# ttl2rs485.net
KiCad netlist of a schematic drawn in Altium Designer
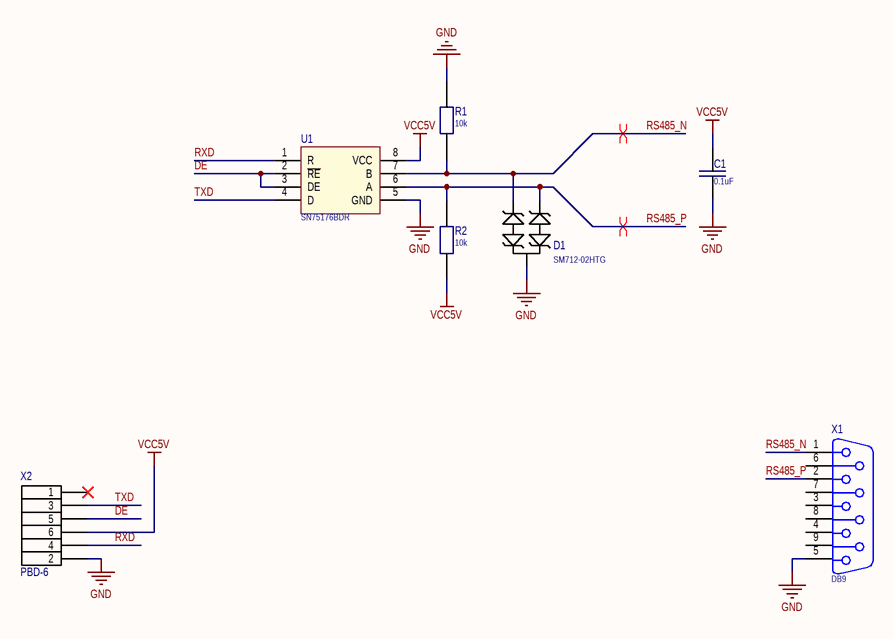
[diagram p0: ttl2rs485.SchDoc]

(export (version "E")
  (design (tool "Eeschema 10.0.6"))
  (components
    (comp (ref "C1")
      (value "0.1uF")
      (footprint "C_0603")
      (description "Capacitor")
      (fields (field (name "PART NUMBER") "CC0603KPX7R9BB104"))
      (libsource (lib "capacitors") (part "CAP_SMD"))
    )
    (comp (ref "D1")
      (value "SM712-02HTG")
      (footprint "diode:SOT23")
      (description "ESD")
      (libsource (lib "diode") (part "ESD"))
    )
    (comp (ref "R1")
      (value "10k")
      (footprint "R_0603")
      (description "Resistor")
      (fields (field (name "PART NUMBER") "RC0603FR-0710KL"))
      (libsource (lib "resistors") (part "RES_SMD"))
    )
    (comp (ref "R2")
      (value "10k")
      (footprint "R_0603")
      (description "Resistor")
      (fields (field (name "PART NUMBER") "RC0603FR-0710KL"))
      (libsource (lib "resistors") (part "RES_SMD"))
    )
    (comp (ref "U1")
      (value "SN75176BDR")
      (footprint "SO-8")
      (description "RS485 Half Duplex Convertor")
      (libsource (lib "discret_ic") (part "SN75176BDR"))
    )
    (comp (ref "X1")
      (value "DB9")
      (footprint "DB9_template")
      (description "Connector")
      (libsource (lib "connectors_socets") (part "DB9_template"))
    )
    (comp (ref "X2")
      (value "PBD-6")
      (footprint "PBD-6-sideways")
      (description "Header, 6-Pin, Dual row")
      (libsource (lib "connectors_socets") (part "PBD-6"))
    )
  )
  (nets
    (net (code "1") (name "/DE") (class "Default")
      (node (ref "U1") (pin "2") (pinfunction "~{RE}_2") (pintype "passive"))
      (node (ref "U1") (pin "3") (pinfunction "DE_3") (pintype "passive"))
      (node (ref "X2") (pin "5") (pinfunction "5_5") (pintype "passive"))
    )
    (net (code "2") (name "/RS485_N") (class "Default")
      (node (ref "D1") (pin "1") (pinfunction "1_1") (pintype "passive"))
      (node (ref "R1") (pin "1") (pinfunction "1_1") (pintype "passive"))
      (node (ref "U1") (pin "7") (pinfunction "B_7") (pintype "passive"))
      (node (ref "X1") (pin "1") (pinfunction "1_1") (pintype "passive"))
    )
    (net (code "3") (name "/RS485_P") (class "Default")
      (node (ref "D1") (pin "2") (pinfunction "2_2") (pintype "passive"))
      (node (ref "R2") (pin "2") (pinfunction "2_2") (pintype "passive"))
      (node (ref "U1") (pin "6") (pinfunction "A_6") (pintype "passive"))
      (node (ref "X1") (pin "2") (pinfunction "2_2") (pintype "passive"))
    )
    (net (code "4") (name "/RXD") (class "Default")
      (node (ref "U1") (pin "1") (pinfunction "R_1") (pintype "passive"))
      (node (ref "X2") (pin "4") (pinfunction "4_4") (pintype "passive"))
    )
    (net (code "5") (name "/TXD") (class "Default")
      (node (ref "U1") (pin "4") (pinfunction "D_4") (pintype "passive"))
      (node (ref "X2") (pin "3") (pinfunction "3_3") (pintype "passive"))
    )
    (net (code "6") (name "GND") (class "Default")
      (node (ref "C1") (pin "1") (pinfunction "1_1") (pintype "passive"))
      (node (ref "D1") (pin "3") (pinfunction "3_3") (pintype "passive"))
      (node (ref "R1") (pin "2") (pinfunction "2_2") (pintype "passive"))
      (node (ref "U1") (pin "5") (pinfunction "GND_5") (pintype "passive"))
      (node (ref "X1") (pin "5") (pinfunction "5_5") (pintype "passive"))
      (node (ref "X2") (pin "2") (pinfunction "2_2") (pintype "passive"))
    )
    (net (code "7") (name "VCC5V") (class "Default")
      (node (ref "C1") (pin "2") (pinfunction "2_2") (pintype "passive"))
      (node (ref "R2") (pin "1") (pinfunction "1_1") (pintype "passive"))
      (node (ref "U1") (pin "8") (pinfunction "VCC_8") (pintype "passive"))
      (node (ref "X2") (pin "6") (pinfunction "6_6") (pintype "passive"))
    )
    (net (code "8") (name "unconnected-(X1-Pad3)") (class "Default")
      (node (ref "X1") (pin "3") (pinfunction "3_3") (pintype "passive"))
    )
    (net (code "9") (name "unconnected-(X1-Pad4)") (class "Default")
      (node (ref "X1") (pin "4") (pinfunction "4_4") (pintype "passive"))
    )
    (net (code "10") (name "unconnected-(X1-Pad6)") (class "Default")
      (node (ref "X1") (pin "6") (pinfunction "6_6") (pintype "passive"))
    )
    (net (code "11") (name "unconnected-(X1-Pad7)") (class "Default")
      (node (ref "X1") (pin "7") (pinfunction "7_7") (pintype "passive"))
    )
    (net (code "12") (name "unconnected-(X1-Pad8)") (class "Default")
      (node (ref "X1") (pin "8") (pinfunction "8_8") (pintype "passive"))
    )
    (net (code "13") (name "unconnected-(X1-Pad9)") (class "Default")
      (node (ref "X1") (pin "9") (pinfunction "9_9") (pintype "passive"))
    )
    (net (code "14") (name "unconnected-(X2-Pad1)") (class "Default")
      (node (ref "X2") (pin "1") (pinfunction "1_1") (pintype "passive+no_connect"))
    )
  )
)
